# input3.net
KiCad netlist of a schematic drawn in Altium Designer
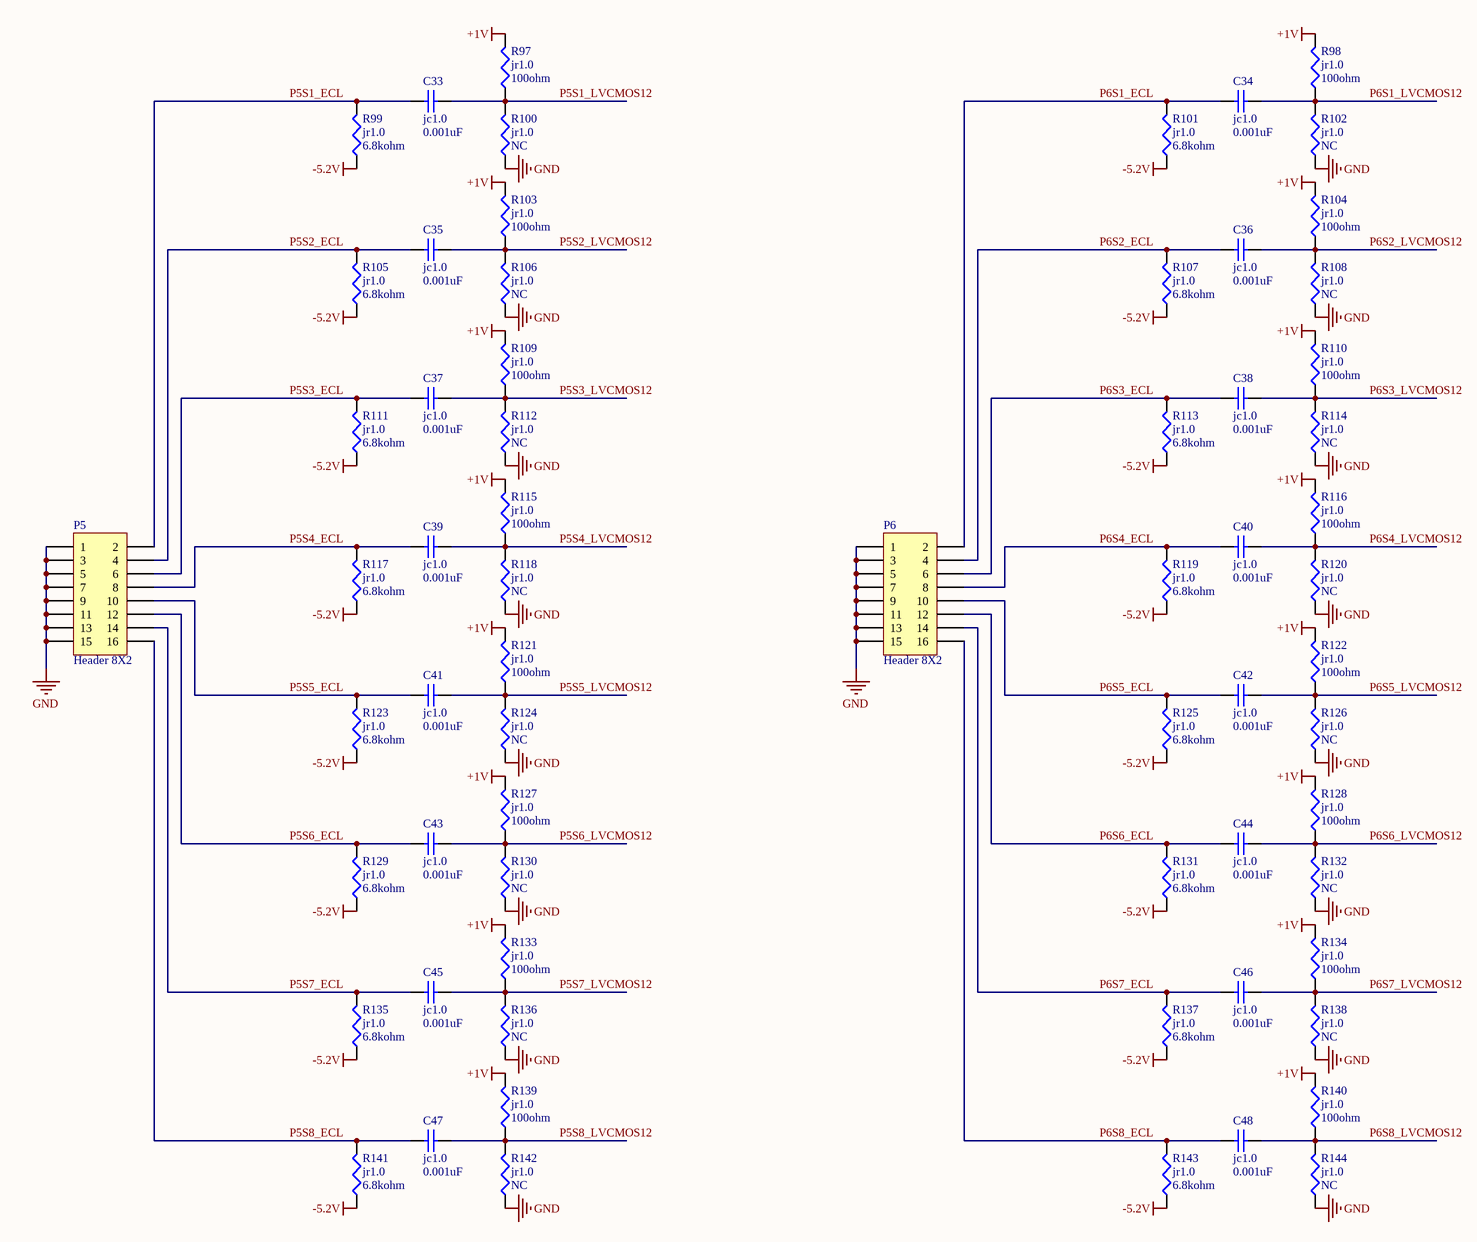
[diagram p0: input3.SchDoc]

(export (version "E")
  (design (tool "Eeschema 10.0.6"))
  (components
    (comp (ref "C33")
      (value "jc1.0")
      (footprint "0402")
      (description "Capacitor")
      (fields (field (name "ALTIUM_VALUE") "0.001uF") (field (name "PUBLISHER") "Altium Limited"))
      (libsource (lib "LIB01DXP2006SchLib") (part "Cap"))
    )
    (comp (ref "C34")
      (value "jc1.0")
      (footprint "0402")
      (description "Capacitor")
      (fields (field (name "ALTIUM_VALUE") "0.001uF") (field (name "PUBLISHER") "Altium Limited"))
      (libsource (lib "LIB01DXP2006SchLib") (part "Cap"))
    )
    (comp (ref "C35")
      (value "jc1.0")
      (footprint "0402")
      (description "Capacitor")
      (fields (field (name "ALTIUM_VALUE") "0.001uF") (field (name "PUBLISHER") "Altium Limited"))
      (libsource (lib "LIB01DXP2006SchLib") (part "Cap"))
    )
    (comp (ref "C36")
      (value "jc1.0")
      (footprint "0402")
      (description "Capacitor")
      (fields (field (name "ALTIUM_VALUE") "0.001uF") (field (name "PUBLISHER") "Altium Limited"))
      (libsource (lib "LIB01DXP2006SchLib") (part "Cap"))
    )
    (comp (ref "C37")
      (value "jc1.0")
      (footprint "0402")
      (description "Capacitor")
      (fields (field (name "ALTIUM_VALUE") "0.001uF") (field (name "PUBLISHER") "Altium Limited"))
      (libsource (lib "LIB01DXP2006SchLib") (part "Cap"))
    )
    (comp (ref "C38")
      (value "jc1.0")
      (footprint "0402")
      (description "Capacitor")
      (fields (field (name "ALTIUM_VALUE") "0.001uF") (field (name "PUBLISHER") "Altium Limited"))
      (libsource (lib "LIB01DXP2006SchLib") (part "Cap"))
    )
    (comp (ref "C39")
      (value "jc1.0")
      (footprint "0402")
      (description "Capacitor")
      (fields (field (name "ALTIUM_VALUE") "0.001uF") (field (name "PUBLISHER") "Altium Limited"))
      (libsource (lib "LIB01DXP2006SchLib") (part "Cap"))
    )
    (comp (ref "C40")
      (value "jc1.0")
      (footprint "0402")
      (description "Capacitor")
      (fields (field (name "ALTIUM_VALUE") "0.001uF") (field (name "PUBLISHER") "Altium Limited"))
      (libsource (lib "LIB01DXP2006SchLib") (part "Cap"))
    )
    (comp (ref "C41")
      (value "jc1.0")
      (footprint "0402")
      (description "Capacitor")
      (fields (field (name "ALTIUM_VALUE") "0.001uF") (field (name "PUBLISHER") "Altium Limited"))
      (libsource (lib "LIB01DXP2006SchLib") (part "Cap"))
    )
    (comp (ref "C42")
      (value "jc1.0")
      (footprint "0402")
      (description "Capacitor")
      (fields (field (name "ALTIUM_VALUE") "0.001uF") (field (name "PUBLISHER") "Altium Limited"))
      (libsource (lib "LIB01DXP2006SchLib") (part "Cap"))
    )
    (comp (ref "C43")
      (value "jc1.0")
      (footprint "0402")
      (description "Capacitor")
      (fields (field (name "ALTIUM_VALUE") "0.001uF") (field (name "PUBLISHER") "Altium Limited"))
      (libsource (lib "LIB01DXP2006SchLib") (part "Cap"))
    )
    (comp (ref "C44")
      (value "jc1.0")
      (footprint "0402")
      (description "Capacitor")
      (fields (field (name "ALTIUM_VALUE") "0.001uF") (field (name "PUBLISHER") "Altium Limited"))
      (libsource (lib "LIB01DXP2006SchLib") (part "Cap"))
    )
    (comp (ref "C45")
      (value "jc1.0")
      (footprint "0402")
      (description "Capacitor")
      (fields (field (name "ALTIUM_VALUE") "0.001uF") (field (name "PUBLISHER") "Altium Limited"))
      (libsource (lib "LIB01DXP2006SchLib") (part "Cap"))
    )
    (comp (ref "C46")
      (value "jc1.0")
      (footprint "0402")
      (description "Capacitor")
      (fields (field (name "ALTIUM_VALUE") "0.001uF") (field (name "PUBLISHER") "Altium Limited"))
      (libsource (lib "LIB01DXP2006SchLib") (part "Cap"))
    )
    (comp (ref "C47")
      (value "jc1.0")
      (footprint "0402")
      (description "Capacitor")
      (fields (field (name "ALTIUM_VALUE") "0.001uF") (field (name "PUBLISHER") "Altium Limited"))
      (libsource (lib "LIB01DXP2006SchLib") (part "Cap"))
    )
    (comp (ref "C48")
      (value "jc1.0")
      (footprint "0402")
      (description "Capacitor")
      (fields (field (name "ALTIUM_VALUE") "0.001uF") (field (name "PUBLISHER") "Altium Limited"))
      (libsource (lib "LIB01DXP2006SchLib") (part "Cap"))
    )
    (comp (ref "P5")
      (value "Header 8X2")
      (footprint "HDR2X8")
      (description "Header, 8-Pin, Dual row")
      (fields (field (name "PUBLISHER") "Altium Limited"))
      (libsource (lib "Miscellaneous Connectors") (part "Header 8X2"))
    )
    (comp (ref "P6")
      (value "Header 8X2")
      (footprint "HDR2X8")
      (description "Header, 8-Pin, Dual row")
      (fields (field (name "PUBLISHER") "Altium Limited"))
      (libsource (lib "Miscellaneous Connectors") (part "Header 8X2"))
    )
    (comp (ref "R97")
      (value "jr1.0")
      (footprint "0402")
      (description "Resistor")
      (fields (field (name "ALTIUM_VALUE") "100ohm") (field (name "PUBLISHER") "Altium Limited"))
      (libsource (lib "LIB01DXP2006SchLib") (part "Res"))
    )
    (comp (ref "R98")
      (value "jr1.0")
      (footprint "0402")
      (description "Resistor")
      (fields (field (name "ALTIUM_VALUE") "100ohm") (field (name "PUBLISHER") "Altium Limited"))
      (libsource (lib "LIB01DXP2006SchLib") (part "Res"))
    )
    (comp (ref "R99")
      (value "jr1.0")
      (footprint "0402")
      (description "Resistor")
      (fields (field (name "ALTIUM_VALUE") "6.8kohm") (field (name "PUBLISHER") "Altium Limited"))
      (libsource (lib "LIB01DXP2006SchLib") (part "Res"))
    )
    (comp (ref "R100")
      (value "jr1.0")
      (footprint "0402")
      (description "Resistor")
      (fields (field (name "ALTIUM_VALUE") "NC") (field (name "PUBLISHER") "Altium Limited"))
      (libsource (lib "LIB01DXP2006SchLib") (part "Res"))
    )
    (comp (ref "R101")
      (value "jr1.0")
      (footprint "0402")
      (description "Resistor")
      (fields (field (name "ALTIUM_VALUE") "6.8kohm") (field (name "PUBLISHER") "Altium Limited"))
      (libsource (lib "LIB01DXP2006SchLib") (part "Res"))
    )
    (comp (ref "R102")
      (value "jr1.0")
      (footprint "0402")
      (description "Resistor")
      (fields (field (name "ALTIUM_VALUE") "NC") (field (name "PUBLISHER") "Altium Limited"))
      (libsource (lib "LIB01DXP2006SchLib") (part "Res"))
    )
    (comp (ref "R103")
      (value "jr1.0")
      (footprint "0402")
      (description "Resistor")
      (fields (field (name "ALTIUM_VALUE") "100ohm") (field (name "PUBLISHER") "Altium Limited"))
      (libsource (lib "LIB01DXP2006SchLib") (part "Res"))
    )
    (comp (ref "R104")
      (value "jr1.0")
      (footprint "0402")
      (description "Resistor")
      (fields (field (name "ALTIUM_VALUE") "100ohm") (field (name "PUBLISHER") "Altium Limited"))
      (libsource (lib "LIB01DXP2006SchLib") (part "Res"))
    )
    (comp (ref "R105")
      (value "jr1.0")
      (footprint "0402")
      (description "Resistor")
      (fields (field (name "ALTIUM_VALUE") "6.8kohm") (field (name "PUBLISHER") "Altium Limited"))
      (libsource (lib "LIB01DXP2006SchLib") (part "Res"))
    )
    (comp (ref "R106")
      (value "jr1.0")
      (footprint "0402")
      (description "Resistor")
      (fields (field (name "ALTIUM_VALUE") "NC") (field (name "PUBLISHER") "Altium Limited"))
      (libsource (lib "LIB01DXP2006SchLib") (part "Res"))
    )
    (comp (ref "R107")
      (value "jr1.0")
      (footprint "0402")
      (description "Resistor")
      (fields (field (name "ALTIUM_VALUE") "6.8kohm") (field (name "PUBLISHER") "Altium Limited"))
      (libsource (lib "LIB01DXP2006SchLib") (part "Res"))
    )
    (comp (ref "R108")
      (value "jr1.0")
      (footprint "0402")
      (description "Resistor")
      (fields (field (name "ALTIUM_VALUE") "NC") (field (name "PUBLISHER") "Altium Limited"))
      (libsource (lib "LIB01DXP2006SchLib") (part "Res"))
    )
    (comp (ref "R109")
      (value "jr1.0")
      (footprint "0402")
      (description "Resistor")
      (fields (field (name "ALTIUM_VALUE") "100ohm") (field (name "PUBLISHER") "Altium Limited"))
      (libsource (lib "LIB01DXP2006SchLib") (part "Res"))
    )
    (comp (ref "R110")
      (value "jr1.0")
      (footprint "0402")
      (description "Resistor")
      (fields (field (name "ALTIUM_VALUE") "100ohm") (field (name "PUBLISHER") "Altium Limited"))
      (libsource (lib "LIB01DXP2006SchLib") (part "Res"))
    )
    (comp (ref "R111")
      (value "jr1.0")
      (footprint "0402")
      (description "Resistor")
      (fields (field (name "ALTIUM_VALUE") "6.8kohm") (field (name "PUBLISHER") "Altium Limited"))
      (libsource (lib "LIB01DXP2006SchLib") (part "Res"))
    )
    (comp (ref "R112")
      (value "jr1.0")
      (footprint "0402")
      (description "Resistor")
      (fields (field (name "ALTIUM_VALUE") "NC") (field (name "PUBLISHER") "Altium Limited"))
      (libsource (lib "LIB01DXP2006SchLib") (part "Res"))
    )
    (comp (ref "R113")
      (value "jr1.0")
      (footprint "0402")
      (description "Resistor")
      (fields (field (name "ALTIUM_VALUE") "6.8kohm") (field (name "PUBLISHER") "Altium Limited"))
      (libsource (lib "LIB01DXP2006SchLib") (part "Res"))
    )
    (comp (ref "R114")
      (value "jr1.0")
      (footprint "0402")
      (description "Resistor")
      (fields (field (name "ALTIUM_VALUE") "NC") (field (name "PUBLISHER") "Altium Limited"))
      (libsource (lib "LIB01DXP2006SchLib") (part "Res"))
    )
    (comp (ref "R115")
      (value "jr1.0")
      (footprint "0402")
      (description "Resistor")
      (fields (field (name "ALTIUM_VALUE") "100ohm") (field (name "PUBLISHER") "Altium Limited"))
      (libsource (lib "LIB01DXP2006SchLib") (part "Res"))
    )
    (comp (ref "R116")
      (value "jr1.0")
      (footprint "0402")
      (description "Resistor")
      (fields (field (name "ALTIUM_VALUE") "100ohm") (field (name "PUBLISHER") "Altium Limited"))
      (libsource (lib "LIB01DXP2006SchLib") (part "Res"))
    )
    (comp (ref "R117")
      (value "jr1.0")
      (footprint "0402")
      (description "Resistor")
      (fields (field (name "ALTIUM_VALUE") "6.8kohm") (field (name "PUBLISHER") "Altium Limited"))
      (libsource (lib "LIB01DXP2006SchLib") (part "Res"))
    )
    (comp (ref "R118")
      (value "jr1.0")
      (footprint "0402")
      (description "Resistor")
      (fields (field (name "ALTIUM_VALUE") "NC") (field (name "PUBLISHER") "Altium Limited"))
      (libsource (lib "LIB01DXP2006SchLib") (part "Res"))
    )
    (comp (ref "R119")
      (value "jr1.0")
      (footprint "0402")
      (description "Resistor")
      (fields (field (name "ALTIUM_VALUE") "6.8kohm") (field (name "PUBLISHER") "Altium Limited"))
      (libsource (lib "LIB01DXP2006SchLib") (part "Res"))
    )
    (comp (ref "R120")
      (value "jr1.0")
      (footprint "0402")
      (description "Resistor")
      (fields (field (name "ALTIUM_VALUE") "NC") (field (name "PUBLISHER") "Altium Limited"))
      (libsource (lib "LIB01DXP2006SchLib") (part "Res"))
    )
    (comp (ref "R121")
      (value "jr1.0")
      (footprint "0402")
      (description "Resistor")
      (fields (field (name "ALTIUM_VALUE") "100ohm") (field (name "PUBLISHER") "Altium Limited"))
      (libsource (lib "LIB01DXP2006SchLib") (part "Res"))
    )
    (comp (ref "R122")
      (value "jr1.0")
      (footprint "0402")
      (description "Resistor")
      (fields (field (name "ALTIUM_VALUE") "100ohm") (field (name "PUBLISHER") "Altium Limited"))
      (libsource (lib "LIB01DXP2006SchLib") (part "Res"))
    )
    (comp (ref "R123")
      (value "jr1.0")
      (footprint "0402")
      (description "Resistor")
      (fields (field (name "ALTIUM_VALUE") "6.8kohm") (field (name "PUBLISHER") "Altium Limited"))
      (libsource (lib "LIB01DXP2006SchLib") (part "Res"))
    )
    (comp (ref "R124")
      (value "jr1.0")
      (footprint "0402")
      (description "Resistor")
      (fields (field (name "ALTIUM_VALUE") "NC") (field (name "PUBLISHER") "Altium Limited"))
      (libsource (lib "LIB01DXP2006SchLib") (part "Res"))
    )
    (comp (ref "R125")
      (value "jr1.0")
      (footprint "0402")
      (description "Resistor")
      (fields (field (name "ALTIUM_VALUE") "6.8kohm") (field (name "PUBLISHER") "Altium Limited"))
      (libsource (lib "LIB01DXP2006SchLib") (part "Res"))
    )
    (comp (ref "R126")
      (value "jr1.0")
      (footprint "0402")
      (description "Resistor")
      (fields (field (name "ALTIUM_VALUE") "NC") (field (name "PUBLISHER") "Altium Limited"))
      (libsource (lib "LIB01DXP2006SchLib") (part "Res"))
    )
    (comp (ref "R127")
      (value "jr1.0")
      (footprint "0402")
      (description "Resistor")
      (fields (field (name "ALTIUM_VALUE") "100ohm") (field (name "PUBLISHER") "Altium Limited"))
      (libsource (lib "LIB01DXP2006SchLib") (part "Res"))
    )
    (comp (ref "R128")
      (value "jr1.0")
      (footprint "0402")
      (description "Resistor")
      (fields (field (name "ALTIUM_VALUE") "100ohm") (field (name "PUBLISHER") "Altium Limited"))
      (libsource (lib "LIB01DXP2006SchLib") (part "Res"))
    )
    (comp (ref "R129")
      (value "jr1.0")
      (footprint "0402")
      (description "Resistor")
      (fields (field (name "ALTIUM_VALUE") "6.8kohm") (field (name "PUBLISHER") "Altium Limited"))
      (libsource (lib "LIB01DXP2006SchLib") (part "Res"))
    )
    (comp (ref "R130")
      (value "jr1.0")
      (footprint "0402")
      (description "Resistor")
      (fields (field (name "ALTIUM_VALUE") "NC") (field (name "PUBLISHER") "Altium Limited"))
      (libsource (lib "LIB01DXP2006SchLib") (part "Res"))
    )
    (comp (ref "R131")
      (value "jr1.0")
      (footprint "0402")
      (description "Resistor")
      (fields (field (name "ALTIUM_VALUE") "6.8kohm") (field (name "PUBLISHER") "Altium Limited"))
      (libsource (lib "LIB01DXP2006SchLib") (part "Res"))
    )
    (comp (ref "R132")
      (value "jr1.0")
      (footprint "0402")
      (description "Resistor")
      (fields (field (name "ALTIUM_VALUE") "NC") (field (name "PUBLISHER") "Altium Limited"))
      (libsource (lib "LIB01DXP2006SchLib") (part "Res"))
    )
    (comp (ref "R133")
      (value "jr1.0")
      (footprint "0402")
      (description "Resistor")
      (fields (field (name "ALTIUM_VALUE") "100ohm") (field (name "PUBLISHER") "Altium Limited"))
      (libsource (lib "LIB01DXP2006SchLib") (part "Res"))
    )
    (comp (ref "R134")
      (value "jr1.0")
      (footprint "0402")
      (description "Resistor")
      (fields (field (name "ALTIUM_VALUE") "100ohm") (field (name "PUBLISHER") "Altium Limited"))
      (libsource (lib "LIB01DXP2006SchLib") (part "Res"))
    )
    (comp (ref "R135")
      (value "jr1.0")
      (footprint "0402")
      (description "Resistor")
      (fields (field (name "ALTIUM_VALUE") "6.8kohm") (field (name "PUBLISHER") "Altium Limited"))
      (libsource (lib "LIB01DXP2006SchLib") (part "Res"))
    )
    (comp (ref "R136")
      (value "jr1.0")
      (footprint "0402")
      (description "Resistor")
      (fields (field (name "ALTIUM_VALUE") "NC") (field (name "PUBLISHER") "Altium Limited"))
      (libsource (lib "LIB01DXP2006SchLib") (part "Res"))
    )
    (comp (ref "R137")
      (value "jr1.0")
      (footprint "0402")
      (description "Resistor")
      (fields (field (name "ALTIUM_VALUE") "6.8kohm") (field (name "PUBLISHER") "Altium Limited"))
      (libsource (lib "LIB01DXP2006SchLib") (part "Res"))
    )
    (comp (ref "R138")
      (value "jr1.0")
      (footprint "0402")
      (description "Resistor")
      (fields (field (name "ALTIUM_VALUE") "NC") (field (name "PUBLISHER") "Altium Limited"))
      (libsource (lib "LIB01DXP2006SchLib") (part "Res"))
    )
    (comp (ref "R139")
      (value "jr1.0")
      (footprint "0402")
      (description "Resistor")
      (fields (field (name "ALTIUM_VALUE") "100ohm") (field (name "PUBLISHER") "Altium Limited"))
      (libsource (lib "LIB01DXP2006SchLib") (part "Res"))
    )
    (comp (ref "R140")
      (value "jr1.0")
      (footprint "0402")
      (description "Resistor")
      (fields (field (name "ALTIUM_VALUE") "100ohm") (field (name "PUBLISHER") "Altium Limited"))
      (libsource (lib "LIB01DXP2006SchLib") (part "Res"))
    )
    (comp (ref "R141")
      (value "jr1.0")
      (footprint "0402")
      (description "Resistor")
      (fields (field (name "ALTIUM_VALUE") "6.8kohm") (field (name "PUBLISHER") "Altium Limited"))
      (libsource (lib "LIB01DXP2006SchLib") (part "Res"))
    )
    (comp (ref "R142")
      (value "jr1.0")
      (footprint "0402")
      (description "Resistor")
      (fields (field (name "ALTIUM_VALUE") "NC") (field (name "PUBLISHER") "Altium Limited"))
      (libsource (lib "LIB01DXP2006SchLib") (part "Res"))
    )
    (comp (ref "R143")
      (value "jr1.0")
      (footprint "0402")
      (description "Resistor")
      (fields (field (name "ALTIUM_VALUE") "6.8kohm") (field (name "PUBLISHER") "Altium Limited"))
      (libsource (lib "LIB01DXP2006SchLib") (part "Res"))
    )
    (comp (ref "R144")
      (value "jr1.0")
      (footprint "0402")
      (description "Resistor")
      (fields (field (name "ALTIUM_VALUE") "NC") (field (name "PUBLISHER") "Altium Limited"))
      (libsource (lib "LIB01DXP2006SchLib") (part "Res"))
    )
  )
  (nets
    (net (code "1") (name "+1V") (class "Default")
      (node (ref "R103") (pin "2") (pinfunction "2_2") (pintype "passive"))
      (node (ref "R104") (pin "2") (pinfunction "2_2") (pintype "passive"))
      (node (ref "R109") (pin "2") (pinfunction "2_2") (pintype "passive"))
      (node (ref "R110") (pin "2") (pinfunction "2_2") (pintype "passive"))
      (node (ref "R115") (pin "2") (pinfunction "2_2") (pintype "passive"))
      (node (ref "R116") (pin "2") (pinfunction "2_2") (pintype "passive"))
      (node (ref "R121") (pin "2") (pinfunction "2_2") (pintype "passive"))
      (node (ref "R122") (pin "2") (pinfunction "2_2") (pintype "passive"))
      (node (ref "R127") (pin "2") (pinfunction "2_2") (pintype "passive"))
      (node (ref "R128") (pin "2") (pinfunction "2_2") (pintype "passive"))
      (node (ref "R133") (pin "2") (pinfunction "2_2") (pintype "passive"))
      (node (ref "R134") (pin "2") (pinfunction "2_2") (pintype "passive"))
      (node (ref "R139") (pin "2") (pinfunction "2_2") (pintype "passive"))
      (node (ref "R140") (pin "2") (pinfunction "2_2") (pintype "passive"))
      (node (ref "R97") (pin "2") (pinfunction "2_2") (pintype "passive"))
      (node (ref "R98") (pin "2") (pinfunction "2_2") (pintype "passive"))
    )
    (net (code "2") (name "-5.2V") (class "Default")
      (node (ref "R101") (pin "1") (pinfunction "1_1") (pintype "passive"))
      (node (ref "R105") (pin "1") (pinfunction "1_1") (pintype "passive"))
      (node (ref "R107") (pin "1") (pinfunction "1_1") (pintype "passive"))
      (node (ref "R111") (pin "1") (pinfunction "1_1") (pintype "passive"))
      (node (ref "R113") (pin "1") (pinfunction "1_1") (pintype "passive"))
      (node (ref "R117") (pin "1") (pinfunction "1_1") (pintype "passive"))
      (node (ref "R119") (pin "1") (pinfunction "1_1") (pintype "passive"))
      (node (ref "R123") (pin "1") (pinfunction "1_1") (pintype "passive"))
      (node (ref "R125") (pin "1") (pinfunction "1_1") (pintype "passive"))
      (node (ref "R129") (pin "1") (pinfunction "1_1") (pintype "passive"))
      (node (ref "R131") (pin "1") (pinfunction "1_1") (pintype "passive"))
      (node (ref "R135") (pin "1") (pinfunction "1_1") (pintype "passive"))
      (node (ref "R137") (pin "1") (pinfunction "1_1") (pintype "passive"))
      (node (ref "R141") (pin "1") (pinfunction "1_1") (pintype "passive"))
      (node (ref "R143") (pin "1") (pinfunction "1_1") (pintype "passive"))
      (node (ref "R99") (pin "1") (pinfunction "1_1") (pintype "passive"))
    )
    (net (code "3") (name "/P5S1_ECL") (class "Default")
      (node (ref "C33") (pin "1") (pinfunction "1_1") (pintype "passive"))
      (node (ref "P5") (pin "2") (pinfunction "2_2") (pintype "passive"))
      (node (ref "R99") (pin "2") (pinfunction "2_2") (pintype "passive"))
    )
    (net (code "4") (name "/P5S1_LVCMOS12") (class "Default")
      (node (ref "C33") (pin "2") (pinfunction "2_2") (pintype "passive"))
      (node (ref "R100") (pin "2") (pinfunction "2_2") (pintype "passive"))
      (node (ref "R97") (pin "1") (pinfunction "1_1") (pintype "passive"))
    )
    (net (code "5") (name "/P5S2_ECL") (class "Default")
      (node (ref "C35") (pin "1") (pinfunction "1_1") (pintype "passive"))
      (node (ref "P5") (pin "4") (pinfunction "4_4") (pintype "passive"))
      (node (ref "R105") (pin "2") (pinfunction "2_2") (pintype "passive"))
    )
    (net (code "6") (name "/P5S2_LVCMOS12") (class "Default")
      (node (ref "C35") (pin "2") (pinfunction "2_2") (pintype "passive"))
      (node (ref "R103") (pin "1") (pinfunction "1_1") (pintype "passive"))
      (node (ref "R106") (pin "2") (pinfunction "2_2") (pintype "passive"))
    )
    (net (code "7") (name "/P5S3_ECL") (class "Default")
      (node (ref "C37") (pin "1") (pinfunction "1_1") (pintype "passive"))
      (node (ref "P5") (pin "6") (pinfunction "6_6") (pintype "passive"))
      (node (ref "R111") (pin "2") (pinfunction "2_2") (pintype "passive"))
    )
    (net (code "8") (name "/P5S3_LVCMOS12") (class "Default")
      (node (ref "C37") (pin "2") (pinfunction "2_2") (pintype "passive"))
      (node (ref "R109") (pin "1") (pinfunction "1_1") (pintype "passive"))
      (node (ref "R112") (pin "2") (pinfunction "2_2") (pintype "passive"))
    )
    (net (code "9") (name "/P5S4_ECL") (class "Default")
      (node (ref "C39") (pin "1") (pinfunction "1_1") (pintype "passive"))
      (node (ref "P5") (pin "8") (pinfunction "8_8") (pintype "passive"))
      (node (ref "R117") (pin "2") (pinfunction "2_2") (pintype "passive"))
    )
    (net (code "10") (name "/P5S4_LVCMOS12") (class "Default")
      (node (ref "C39") (pin "2") (pinfunction "2_2") (pintype "passive"))
      (node (ref "R115") (pin "1") (pinfunction "1_1") (pintype "passive"))
      (node (ref "R118") (pin "2") (pinfunction "2_2") (pintype "passive"))
    )
    (net (code "11") (name "/P5S5_ECL") (class "Default")
      (node (ref "C41") (pin "1") (pinfunction "1_1") (pintype "passive"))
      (node (ref "P5") (pin "10") (pinfunction "10_10") (pintype "passive"))
      (node (ref "R123") (pin "2") (pinfunction "2_2") (pintype "passive"))
    )
    (net (code "12") (name "/P5S5_LVCMOS12") (class "Default")
      (node (ref "C41") (pin "2") (pinfunction "2_2") (pintype "passive"))
      (node (ref "R121") (pin "1") (pinfunction "1_1") (pintype "passive"))
      (node (ref "R124") (pin "2") (pinfunction "2_2") (pintype "passive"))
    )
    (net (code "13") (name "/P5S6_ECL") (class "Default")
      (node (ref "C43") (pin "1") (pinfunction "1_1") (pintype "passive"))
      (node (ref "P5") (pin "12") (pinfunction "12_12") (pintype "passive"))
      (node (ref "R129") (pin "2") (pinfunction "2_2") (pintype "passive"))
    )
    (net (code "14") (name "/P5S6_LVCMOS12") (class "Default")
      (node (ref "C43") (pin "2") (pinfunction "2_2") (pintype "passive"))
      (node (ref "R127") (pin "1") (pinfunction "1_1") (pintype "passive"))
      (node (ref "R130") (pin "2") (pinfunction "2_2") (pintype "passive"))
    )
    (net (code "15") (name "/P5S7_ECL") (class "Default")
      (node (ref "C45") (pin "1") (pinfunction "1_1") (pintype "passive"))
      (node (ref "P5") (pin "14") (pinfunction "14_14") (pintype "passive"))
      (node (ref "R135") (pin "2") (pinfunction "2_2") (pintype "passive"))
    )
    (net (code "16") (name "/P5S7_LVCMOS12") (class "Default")
      (node (ref "C45") (pin "2") (pinfunction "2_2") (pintype "passive"))
      (node (ref "R133") (pin "1") (pinfunction "1_1") (pintype "passive"))
      (node (ref "R136") (pin "2") (pinfunction "2_2") (pintype "passive"))
    )
    (net (code "17") (name "/P5S8_ECL") (class "Default")
      (node (ref "C47") (pin "1") (pinfunction "1_1") (pintype "passive"))
      (node (ref "P5") (pin "16") (pinfunction "16_16") (pintype "passive"))
      (node (ref "R141") (pin "2") (pinfunction "2_2") (pintype "passive"))
    )
    (net (code "18") (name "/P5S8_LVCMOS12") (class "Default")
      (node (ref "C47") (pin "2") (pinfunction "2_2") (pintype "passive"))
      (node (ref "R139") (pin "1") (pinfunction "1_1") (pintype "passive"))
      (node (ref "R142") (pin "2") (pinfunction "2_2") (pintype "passive"))
    )
    (net (code "19") (name "/P6S1_ECL") (class "Default")
      (node (ref "C34") (pin "1") (pinfunction "1_1") (pintype "passive"))
      (node (ref "P6") (pin "2") (pinfunction "2_2") (pintype "passive"))
      (node (ref "R101") (pin "2") (pinfunction "2_2") (pintype "passive"))
    )
    (net (code "20") (name "/P6S1_LVCMOS12") (class "Default")
      (node (ref "C34") (pin "2") (pinfunction "2_2") (pintype "passive"))
      (node (ref "R102") (pin "2") (pinfunction "2_2") (pintype "passive"))
      (node (ref "R98") (pin "1") (pinfunction "1_1") (pintype "passive"))
    )
    (net (code "21") (name "/P6S2_ECL") (class "Default")
      (node (ref "C36") (pin "1") (pinfunction "1_1") (pintype "passive"))
      (node (ref "P6") (pin "4") (pinfunction "4_4") (pintype "passive"))
      (node (ref "R107") (pin "2") (pinfunction "2_2") (pintype "passive"))
    )
    (net (code "22") (name "/P6S2_LVCMOS12") (class "Default")
      (node (ref "C36") (pin "2") (pinfunction "2_2") (pintype "passive"))
      (node (ref "R104") (pin "1") (pinfunction "1_1") (pintype "passive"))
      (node (ref "R108") (pin "2") (pinfunction "2_2") (pintype "passive"))
    )
    (net (code "23") (name "/P6S3_ECL") (class "Default")
      (node (ref "C38") (pin "1") (pinfunction "1_1") (pintype "passive"))
      (node (ref "P6") (pin "6") (pinfunction "6_6") (pintype "passive"))
      (node (ref "R113") (pin "2") (pinfunction "2_2") (pintype "passive"))
    )
    (net (code "24") (name "/P6S3_LVCMOS12") (class "Default")
      (node (ref "C38") (pin "2") (pinfunction "2_2") (pintype "passive"))
      (node (ref "R110") (pin "1") (pinfunction "1_1") (pintype "passive"))
      (node (ref "R114") (pin "2") (pinfunction "2_2") (pintype "passive"))
    )
    (net (code "25") (name "/P6S4_ECL") (class "Default")
      (node (ref "C40") (pin "1") (pinfunction "1_1") (pintype "passive"))
      (node (ref "P6") (pin "8") (pinfunction "8_8") (pintype "passive"))
      (node (ref "R119") (pin "2") (pinfunction "2_2") (pintype "passive"))
    )
    (net (code "26") (name "/P6S4_LVCMOS12") (class "Default")
      (node (ref "C40") (pin "2") (pinfunction "2_2") (pintype "passive"))
      (node (ref "R116") (pin "1") (pinfunction "1_1") (pintype "passive"))
      (node (ref "R120") (pin "2") (pinfunction "2_2") (pintype "passive"))
    )
    (net (code "27") (name "/P6S5_ECL") (class "Default")
      (node (ref "C42") (pin "1") (pinfunction "1_1") (pintype "passive"))
      (node (ref "P6") (pin "10") (pinfunction "10_10") (pintype "passive"))
      (node (ref "R125") (pin "2") (pinfunction "2_2") (pintype "passive"))
    )
    (net (code "28") (name "/P6S5_LVCMOS12") (class "Default")
      (node (ref "C42") (pin "2") (pinfunction "2_2") (pintype "passive"))
      (node (ref "R122") (pin "1") (pinfunction "1_1") (pintype "passive"))
      (node (ref "R126") (pin "2") (pinfunction "2_2") (pintype "passive"))
    )
    (net (code "29") (name "/P6S6_ECL") (class "Default")
      (node (ref "C44") (pin "1") (pinfunction "1_1") (pintype "passive"))
      (node (ref "P6") (pin "12") (pinfunction "12_12") (pintype "passive"))
      (node (ref "R131") (pin "2") (pinfunction "2_2") (pintype "passive"))
    )
    (net (code "30") (name "/P6S6_LVCMOS12") (class "Default")
      (node (ref "C44") (pin "2") (pinfunction "2_2") (pintype "passive"))
      (node (ref "R128") (pin "1") (pinfunction "1_1") (pintype "passive"))
      (node (ref "R132") (pin "2") (pinfunction "2_2") (pintype "passive"))
    )
    (net (code "31") (name "/P6S7_ECL") (class "Default")
      (node (ref "C46") (pin "1") (pinfunction "1_1") (pintype "passive"))
      (node (ref "P6") (pin "14") (pinfunction "14_14") (pintype "passive"))
      (node (ref "R137") (pin "2") (pinfunction "2_2") (pintype "passive"))
    )
    (net (code "32") (name "/P6S7_LVCMOS12") (class "Default")
      (node (ref "C46") (pin "2") (pinfunction "2_2") (pintype "passive"))
      (node (ref "R134") (pin "1") (pinfunction "1_1") (pintype "passive"))
      (node (ref "R138") (pin "2") (pinfunction "2_2") (pintype "passive"))
    )
    (net (code "33") (name "/P6S8_ECL") (class "Default")
      (node (ref "C48") (pin "1") (pinfunction "1_1") (pintype "passive"))
      (node (ref "P6") (pin "16") (pinfunction "16_16") (pintype "passive"))
      (node (ref "R143") (pin "2") (pinfunction "2_2") (pintype "passive"))
    )
    (net (code "34") (name "/P6S8_LVCMOS12") (class "Default")
      (node (ref "C48") (pin "2") (pinfunction "2_2") (pintype "passive"))
      (node (ref "R140") (pin "1") (pinfunction "1_1") (pintype "passive"))
      (node (ref "R144") (pin "2") (pinfunction "2_2") (pintype "passive"))
    )
    (net (code "35") (name "GND") (class "Default")
      (node (ref "P5") (pin "1") (pinfunction "1_1") (pintype "passive"))
      (node (ref "P5") (pin "11") (pinfunction "11_11") (pintype "passive"))
      (node (ref "P5") (pin "13") (pinfunction "13_13") (pintype "passive"))
      (node (ref "P5") (pin "15") (pinfunction "15_15") (pintype "passive"))
      (node (ref "P5") (pin "3") (pinfunction "3_3") (pintype "passive"))
      (node (ref "P5") (pin "5") (pinfunction "5_5") (pintype "passive"))
      (node (ref "P5") (pin "7") (pinfunction "7_7") (pintype "passive"))
      (node (ref "P5") (pin "9") (pinfunction "9_9") (pintype "passive"))
      (node (ref "P6") (pin "1") (pinfunction "1_1") (pintype "passive"))
      (node (ref "P6") (pin "11") (pinfunction "11_11") (pintype "passive"))
      (node (ref "P6") (pin "13") (pinfunction "13_13") (pintype "passive"))
      (node (ref "P6") (pin "15") (pinfunction "15_15") (pintype "passive"))
      (node (ref "P6") (pin "3") (pinfunction "3_3") (pintype "passive"))
      (node (ref "P6") (pin "5") (pinfunction "5_5") (pintype "passive"))
      (node (ref "P6") (pin "7") (pinfunction "7_7") (pintype "passive"))
      (node (ref "P6") (pin "9") (pinfunction "9_9") (pintype "passive"))
      (node (ref "R100") (pin "1") (pinfunction "1_1") (pintype "passive"))
      (node (ref "R102") (pin "1") (pinfunction "1_1") (pintype "passive"))
      (node (ref "R106") (pin "1") (pinfunction "1_1") (pintype "passive"))
      (node (ref "R108") (pin "1") (pinfunction "1_1") (pintype "passive"))
      (node (ref "R112") (pin "1") (pinfunction "1_1") (pintype "passive"))
      (node (ref "R114") (pin "1") (pinfunction "1_1") (pintype "passive"))
      (node (ref "R118") (pin "1") (pinfunction "1_1") (pintype "passive"))
      (node (ref "R120") (pin "1") (pinfunction "1_1") (pintype "passive"))
      (node (ref "R124") (pin "1") (pinfunction "1_1") (pintype "passive"))
      (node (ref "R126") (pin "1") (pinfunction "1_1") (pintype "passive"))
      (node (ref "R130") (pin "1") (pinfunction "1_1") (pintype "passive"))
      (node (ref "R132") (pin "1") (pinfunction "1_1") (pintype "passive"))
      (node (ref "R136") (pin "1") (pinfunction "1_1") (pintype "passive"))
      (node (ref "R138") (pin "1") (pinfunction "1_1") (pintype "passive"))
      (node (ref "R142") (pin "1") (pinfunction "1_1") (pintype "passive"))
      (node (ref "R144") (pin "1") (pinfunction "1_1") (pintype "passive"))
    )
  )
)
